# output2.net
KiCad netlist of a schematic drawn in Altium Designer
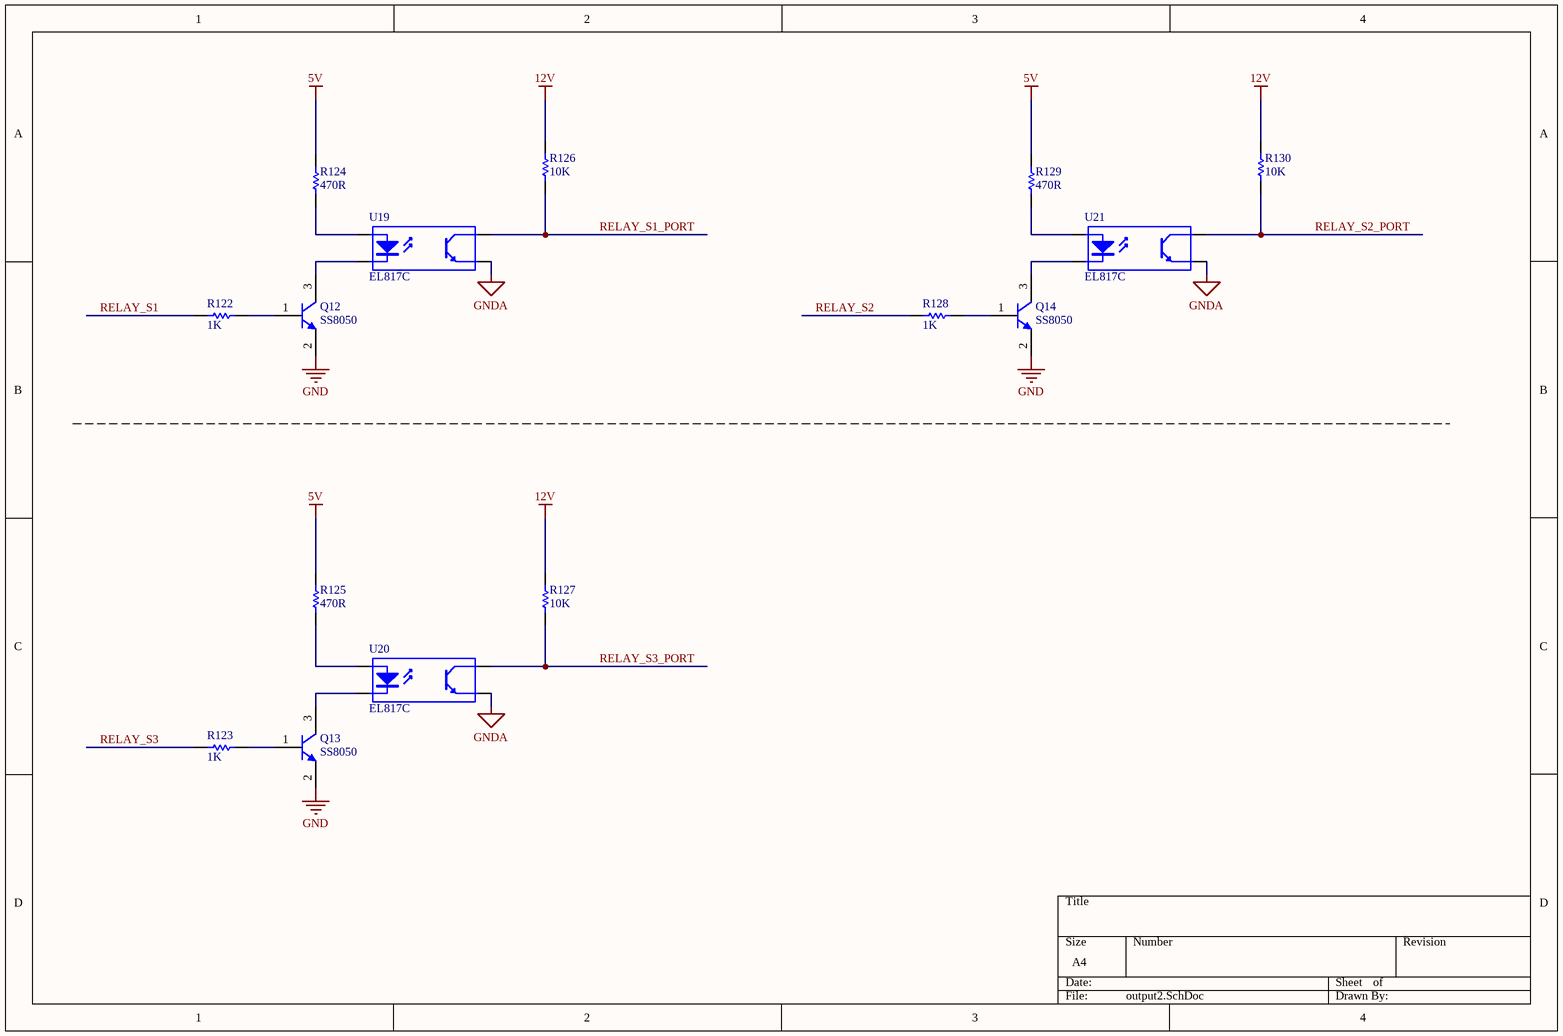
[diagram p0: output2.SchDoc]

(export (version "E")
  (design (tool "Eeschema 10.0.6"))
  (components
    (comp (ref "Q12")
      (value "SS8050")
      (footprint "SOT-23_N")
      (description "NPN BISS Transistor")
      (fields (field (name "PUBLISHER") "Altium Limited"))
      (libsource (lib "Philips Discrete BJT - Low Power") (part "PMMT491A"))
    )
    (comp (ref "Q13")
      (value "SS8050")
      (footprint "SOT-23_N")
      (description "NPN BISS Transistor")
      (fields (field (name "PUBLISHER") "Altium Limited"))
      (libsource (lib "Philips Discrete BJT - Low Power") (part "PMMT491A"))
    )
    (comp (ref "Q14")
      (value "SS8050")
      (footprint "SOT-23_N")
      (description "NPN BISS Transistor")
      (fields (field (name "PUBLISHER") "Altium Limited"))
      (libsource (lib "Philips Discrete BJT - Low Power") (part "PMMT491A"))
    )
    (comp (ref "R122")
      (value "1K")
      (footprint "RESC2012M")
      (description "Resistor")
      (fields (field (name "PUBLISHER") "Altium Limited"))
      (libsource (lib "Miscellaneous Devices") (part "Res1"))
    )
    (comp (ref "R123")
      (value "1K")
      (footprint "RESC2012M")
      (description "Resistor")
      (fields (field (name "PUBLISHER") "Altium Limited"))
      (libsource (lib "Miscellaneous Devices") (part "Res1"))
    )
    (comp (ref "R124")
      (value "470R")
      (footprint "RESC2012M")
      (description "Resistor")
      (fields (field (name "PUBLISHER") "Altium Limited"))
      (libsource (lib "Miscellaneous Devices") (part "Res1"))
    )
    (comp (ref "R125")
      (value "470R")
      (footprint "RESC2012M")
      (description "Resistor")
      (fields (field (name "PUBLISHER") "Altium Limited"))
      (libsource (lib "Miscellaneous Devices") (part "Res1"))
    )
    (comp (ref "R126")
      (value "10K")
      (footprint "RESC2012M")
      (description "Resistor")
      (fields (field (name "PUBLISHER") "Altium Limited"))
      (libsource (lib "Miscellaneous Devices") (part "Res1"))
    )
    (comp (ref "R127")
      (value "10K")
      (footprint "RESC2012M")
      (description "Resistor")
      (fields (field (name "PUBLISHER") "Altium Limited"))
      (libsource (lib "Miscellaneous Devices") (part "Res1"))
    )
    (comp (ref "R128")
      (value "1K")
      (footprint "RESC2012M")
      (description "Resistor")
      (fields (field (name "PUBLISHER") "Altium Limited"))
      (libsource (lib "Miscellaneous Devices") (part "Res1"))
    )
    (comp (ref "R129")
      (value "470R")
      (footprint "RESC2012M")
      (description "Resistor")
      (fields (field (name "PUBLISHER") "Altium Limited"))
      (libsource (lib "Miscellaneous Devices") (part "Res1"))
    )
    (comp (ref "R130")
      (value "10K")
      (footprint "RESC2012M")
      (description "Resistor")
      (fields (field (name "PUBLISHER") "Altium Limited"))
      (libsource (lib "Miscellaneous Devices") (part "Res1"))
    )
    (comp (ref "U19")
      (value "EL817C")
      (footprint "SO-4LA")
      (description "4-Pin Phototransistor Optocoupler")
      (fields (field (name "PUBLISHER") "Altium Limited"))
      (libsource (lib "Miscellaneous Devices") (part "Optoisolator1"))
    )
    (comp (ref "U20")
      (value "EL817C")
      (footprint "SO-4LA")
      (description "4-Pin Phototransistor Optocoupler")
      (fields (field (name "PUBLISHER") "Altium Limited"))
      (libsource (lib "Miscellaneous Devices") (part "Optoisolator1"))
    )
    (comp (ref "U21")
      (value "EL817C")
      (footprint "SO-4LA")
      (description "4-Pin Phototransistor Optocoupler")
      (fields (field (name "PUBLISHER") "Altium Limited"))
      (libsource (lib "Miscellaneous Devices") (part "Optoisolator1"))
    )
  )
  (nets
    (net (code "1") (name "/RELAY_S1") (class "Default")
      (node (ref "R122") (pin "1") (pinfunction "1_1") (pintype "passive"))
    )
    (net (code "2") (name "/RELAY_S1_PORT") (class "Default")
      (node (ref "R126") (pin "1") (pinfunction "1_1") (pintype "passive"))
      (node (ref "U19") (pin "4") (pinfunction "C_4") (pintype "passive"))
    )
    (net (code "3") (name "/RELAY_S2") (class "Default")
      (node (ref "R128") (pin "1") (pinfunction "1_1") (pintype "passive"))
    )
    (net (code "4") (name "/RELAY_S2_PORT") (class "Default")
      (node (ref "R130") (pin "1") (pinfunction "1_1") (pintype "passive"))
      (node (ref "U21") (pin "4") (pinfunction "C_4") (pintype "passive"))
    )
    (net (code "5") (name "/RELAY_S3") (class "Default")
      (node (ref "R123") (pin "1") (pinfunction "1_1") (pintype "passive"))
    )
    (net (code "6") (name "/RELAY_S3_PORT") (class "Default")
      (node (ref "R127") (pin "1") (pinfunction "1_1") (pintype "passive"))
      (node (ref "U20") (pin "4") (pinfunction "C_4") (pintype "passive"))
    )
    (net (code "7") (name "5V") (class "Default")
      (node (ref "R124") (pin "1") (pinfunction "1_1") (pintype "passive"))
      (node (ref "R125") (pin "1") (pinfunction "1_1") (pintype "passive"))
      (node (ref "R129") (pin "1") (pinfunction "1_1") (pintype "passive"))
    )
    (net (code "8") (name "12V") (class "Default")
      (node (ref "R126") (pin "2") (pinfunction "2_2") (pintype "passive"))
      (node (ref "R127") (pin "2") (pinfunction "2_2") (pintype "passive"))
      (node (ref "R130") (pin "2") (pinfunction "2_2") (pintype "passive"))
    )
    (net (code "9") (name "GND") (class "Default")
      (node (ref "Q12") (pin "2") (pinfunction "E_2") (pintype "passive"))
      (node (ref "Q13") (pin "2") (pinfunction "E_2") (pintype "passive"))
      (node (ref "Q14") (pin "2") (pinfunction "E_2") (pintype "passive"))
    )
    (net (code "10") (name "GNDA") (class "Default")
      (node (ref "U19") (pin "3") (pinfunction "E_3") (pintype "passive"))
      (node (ref "U20") (pin "3") (pinfunction "E_3") (pintype "passive"))
      (node (ref "U21") (pin "3") (pinfunction "E_3") (pintype "passive"))
    )
    (net (code "11") (name "Net-(Q12-B)") (class "Default")
      (node (ref "Q12") (pin "1") (pinfunction "B_1") (pintype "passive"))
      (node (ref "R122") (pin "2") (pinfunction "2_2") (pintype "passive"))
    )
    (net (code "12") (name "Net-(Q12-C)") (class "Default")
      (node (ref "Q12") (pin "3") (pinfunction "C_3") (pintype "passive"))
      (node (ref "U19") (pin "2") (pinfunction "K_2") (pintype "passive"))
    )
    (net (code "13") (name "Net-(Q13-B)") (class "Default")
      (node (ref "Q13") (pin "1") (pinfunction "B_1") (pintype "passive"))
      (node (ref "R123") (pin "2") (pinfunction "2_2") (pintype "passive"))
    )
    (net (code "14") (name "Net-(Q13-C)") (class "Default")
      (node (ref "Q13") (pin "3") (pinfunction "C_3") (pintype "passive"))
      (node (ref "U20") (pin "2") (pinfunction "K_2") (pintype "passive"))
    )
    (net (code "15") (name "Net-(Q14-B)") (class "Default")
      (node (ref "Q14") (pin "1") (pinfunction "B_1") (pintype "passive"))
      (node (ref "R128") (pin "2") (pinfunction "2_2") (pintype "passive"))
    )
    (net (code "16") (name "Net-(Q14-C)") (class "Default")
      (node (ref "Q14") (pin "3") (pinfunction "C_3") (pintype "passive"))
      (node (ref "U21") (pin "2") (pinfunction "K_2") (pintype "passive"))
    )
    (net (code "17") (name "Net-(U19-A)") (class "Default")
      (node (ref "R124") (pin "2") (pinfunction "2_2") (pintype "passive"))
      (node (ref "U19") (pin "1") (pinfunction "A_1") (pintype "passive"))
    )
    (net (code "18") (name "Net-(U20-A)") (class "Default")
      (node (ref "R125") (pin "2") (pinfunction "2_2") (pintype "passive"))
      (node (ref "U20") (pin "1") (pinfunction "A_1") (pintype "passive"))
    )
    (net (code "19") (name "Net-(U21-A)") (class "Default")
      (node (ref "R129") (pin "2") (pinfunction "2_2") (pintype "passive"))
      (node (ref "U21") (pin "1") (pinfunction "A_1") (pintype "passive"))
    )
  )
)
